# Master10.net
KiCad netlist of a schematic drawn in EAGLE
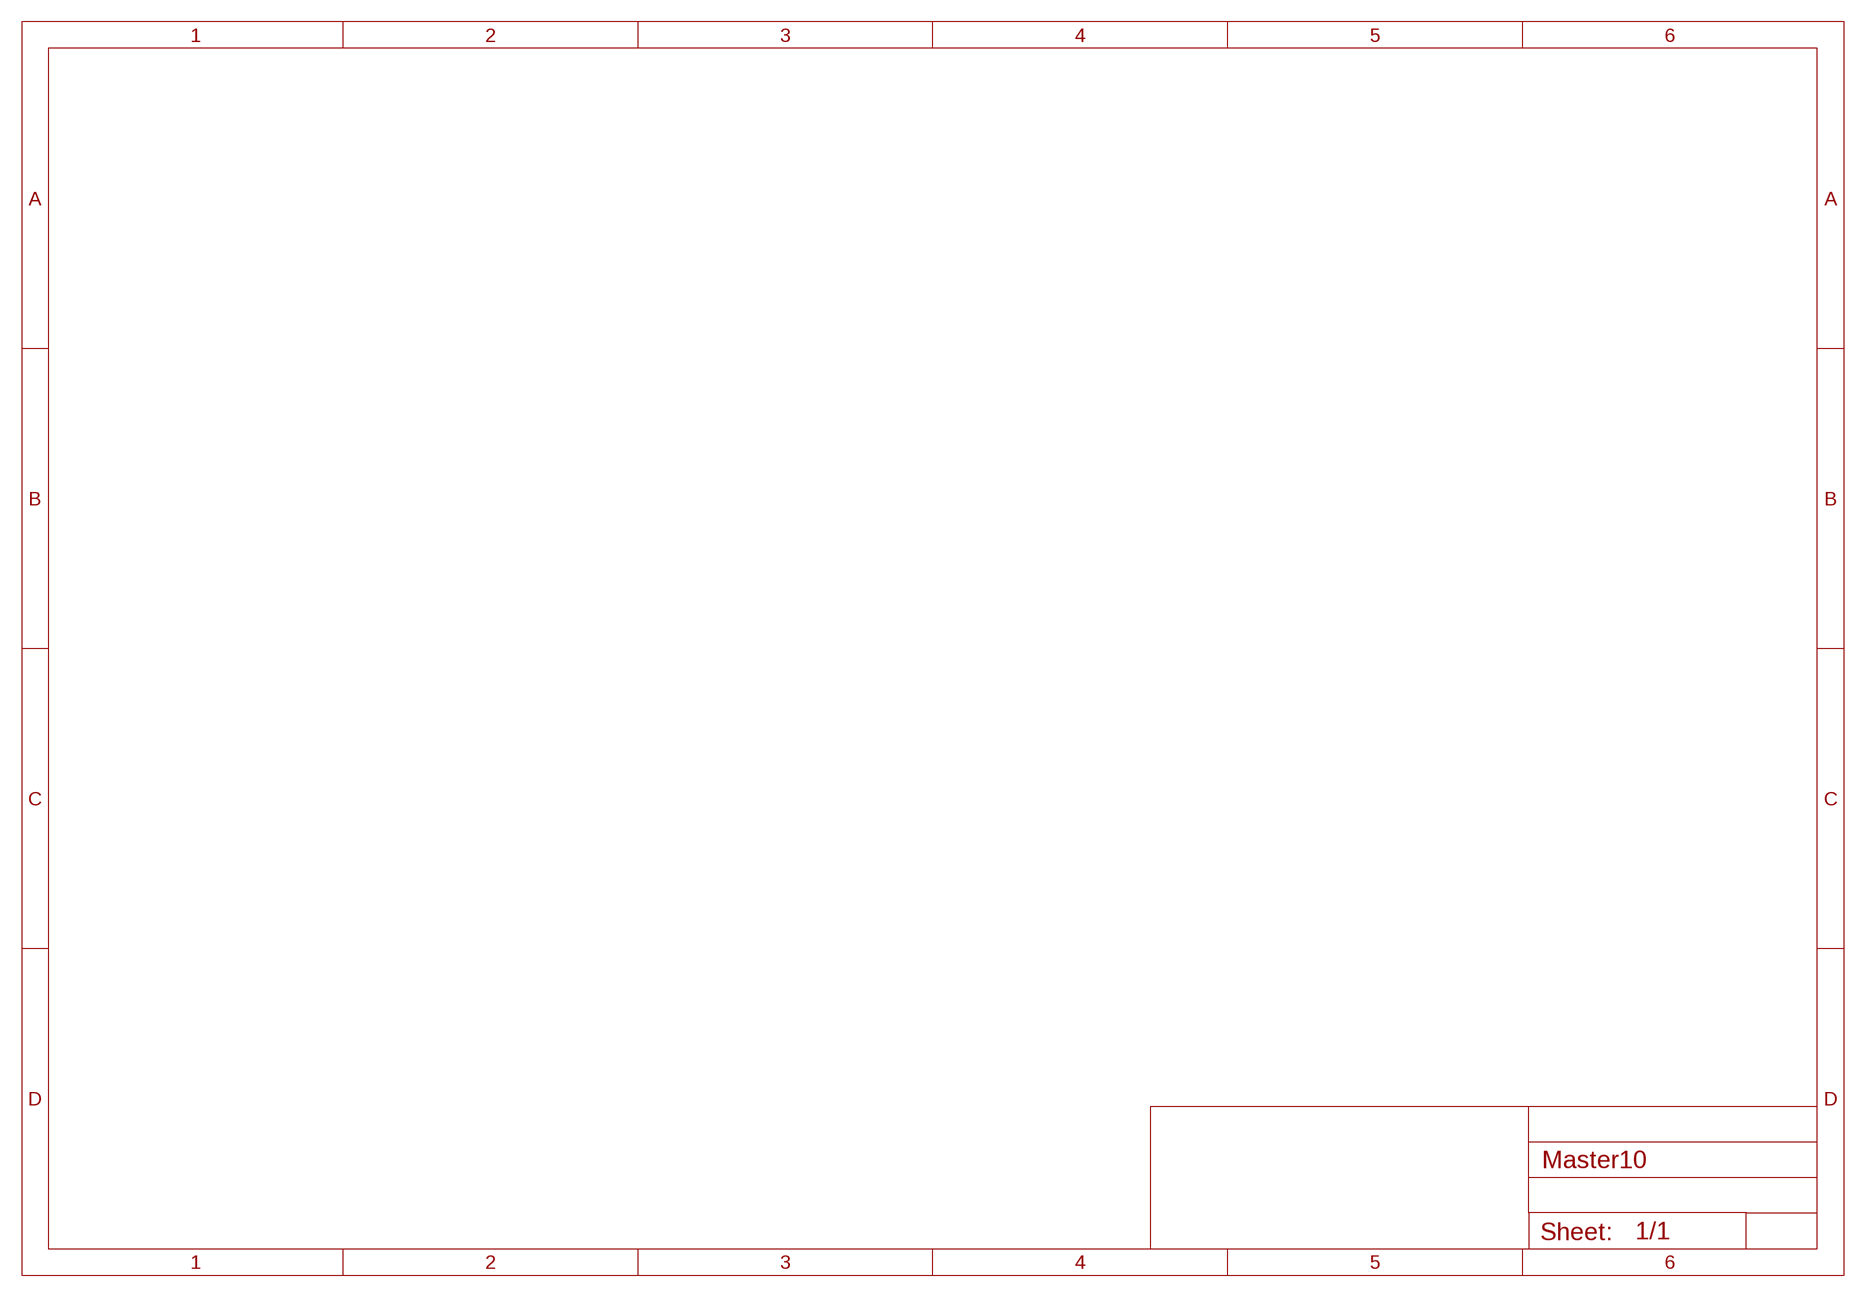
[diagram p0: schematic, sheet 1, part 1 of 2]
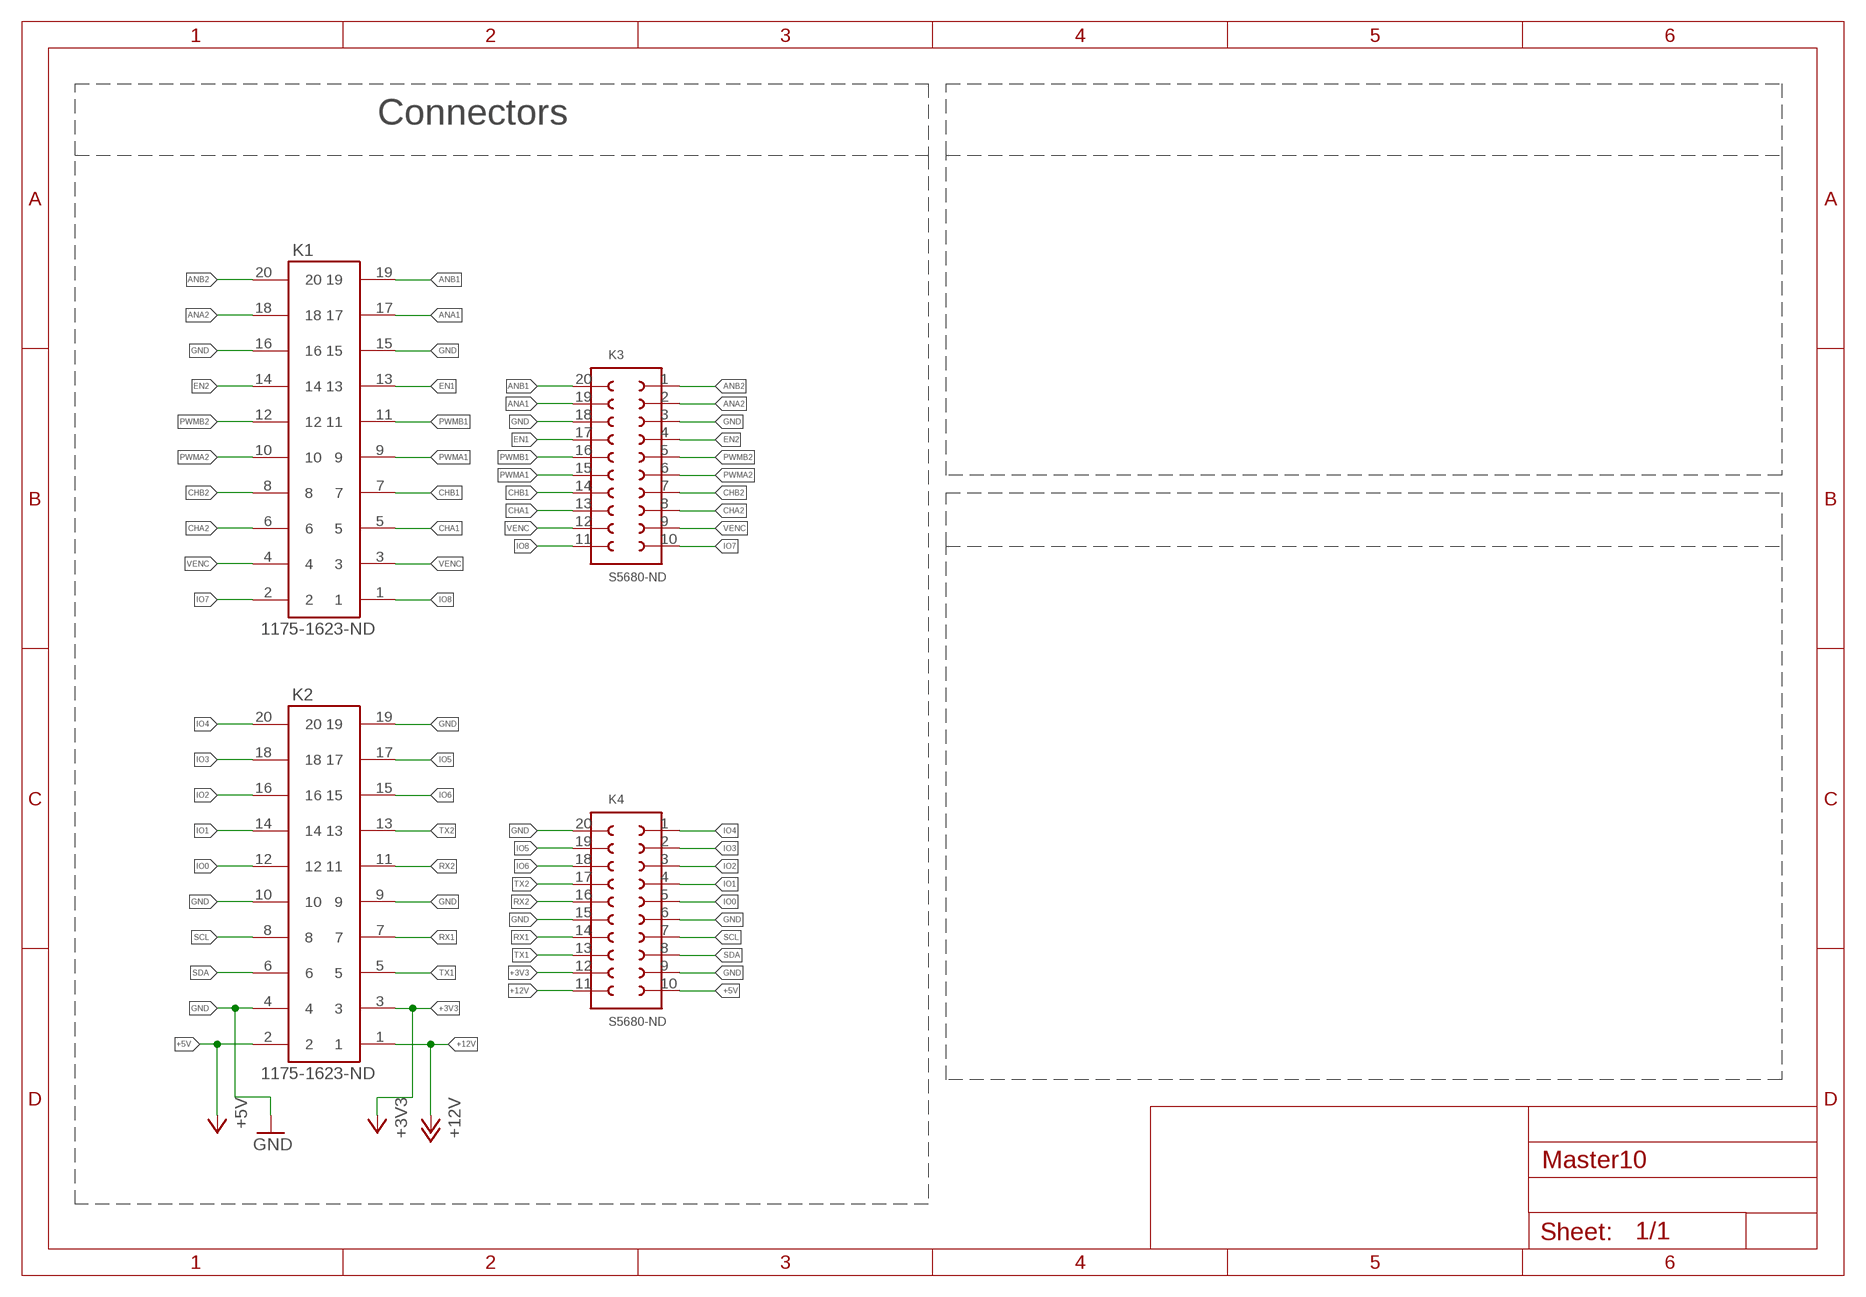
[diagram p1: schematic, sheet 1, part 2 of 2]

(export (version "E")
  (design (tool "Eeschema 10.0.6"))
  (components
    (comp (ref "K1")
      (value "1175-1623-ND")
      (footprint "eagle-import:612X2020621")
      (libsource (lib "eagle-import") (part "612X2020621"))
    )
    (comp (ref "K2")
      (value "1175-1623-ND")
      (footprint "eagle-import:612X2020621")
      (libsource (lib "eagle-import") (part "612X2020621"))
    )
    (comp (ref "K3")
      (value "S5680-ND")
      (footprint "eagle-import:61002021821")
      (libsource (lib "eagle-import") (part "61002021821"))
    )
    (comp (ref "K4")
      (value "S5680-ND")
      (footprint "eagle-import:61002021821")
      (libsource (lib "eagle-import") (part "61002021821"))
    )
  )
  (nets
    (net (code "1") (name "+3V3") (class "Default")
      (node (ref "K2") (pin "3") (pinfunction "3_3") (pintype "passive"))
      (node (ref "K4") (pin "12") (pinfunction "12_12") (pintype "passive"))
    )
    (net (code "2") (name "+5V") (class "Default")
      (node (ref "K2") (pin "2") (pinfunction "2_2") (pintype "passive"))
      (node (ref "K4") (pin "10") (pinfunction "10_10") (pintype "passive"))
    )
    (net (code "3") (name "+12V") (class "Default")
      (node (ref "K2") (pin "1") (pinfunction "1_1") (pintype "passive"))
      (node (ref "K4") (pin "11") (pinfunction "11_11") (pintype "passive"))
    )
    (net (code "4") (name "ANA1") (class "Default")
      (node (ref "K1") (pin "17") (pinfunction "17_17") (pintype "passive"))
      (node (ref "K3") (pin "19") (pinfunction "19_19") (pintype "passive"))
    )
    (net (code "5") (name "ANA2") (class "Default")
      (node (ref "K1") (pin "18") (pinfunction "18_18") (pintype "passive"))
      (node (ref "K3") (pin "2") (pinfunction "2_2") (pintype "passive"))
    )
    (net (code "6") (name "ANB1") (class "Default")
      (node (ref "K1") (pin "19") (pinfunction "19_19") (pintype "passive"))
      (node (ref "K3") (pin "20") (pinfunction "20_20") (pintype "passive"))
    )
    (net (code "7") (name "ANB2") (class "Default")
      (node (ref "K1") (pin "20") (pinfunction "20_20") (pintype "passive"))
      (node (ref "K3") (pin "1") (pinfunction "1_1") (pintype "passive"))
    )
    (net (code "8") (name "CHA1") (class "Default")
      (node (ref "K1") (pin "5") (pinfunction "5_5") (pintype "passive"))
      (node (ref "K3") (pin "13") (pinfunction "13_13") (pintype "passive"))
    )
    (net (code "9") (name "CHA2") (class "Default")
      (node (ref "K1") (pin "6") (pinfunction "6_6") (pintype "passive"))
      (node (ref "K3") (pin "8") (pinfunction "8_8") (pintype "passive"))
    )
    (net (code "10") (name "CHB1") (class "Default")
      (node (ref "K1") (pin "7") (pinfunction "7_7") (pintype "passive"))
      (node (ref "K3") (pin "14") (pinfunction "14_14") (pintype "passive"))
    )
    (net (code "11") (name "CHB2") (class "Default")
      (node (ref "K1") (pin "8") (pinfunction "8_8") (pintype "passive"))
      (node (ref "K3") (pin "7") (pinfunction "7_7") (pintype "passive"))
    )
    (net (code "12") (name "EN1") (class "Default")
      (node (ref "K1") (pin "13") (pinfunction "13_13") (pintype "passive"))
      (node (ref "K3") (pin "17") (pinfunction "17_17") (pintype "passive"))
    )
    (net (code "13") (name "EN2") (class "Default")
      (node (ref "K1") (pin "14") (pinfunction "14_14") (pintype "passive"))
      (node (ref "K3") (pin "4") (pinfunction "4_4") (pintype "passive"))
    )
    (net (code "14") (name "GND") (class "Default")
      (node (ref "K1") (pin "15") (pinfunction "15_15") (pintype "passive"))
      (node (ref "K1") (pin "16") (pinfunction "16_16") (pintype "passive"))
      (node (ref "K2") (pin "10") (pinfunction "10_10") (pintype "passive"))
      (node (ref "K2") (pin "19") (pinfunction "19_19") (pintype "passive"))
      (node (ref "K2") (pin "4") (pinfunction "4_4") (pintype "passive"))
      (node (ref "K2") (pin "9") (pinfunction "9_9") (pintype "passive"))
      (node (ref "K3") (pin "18") (pinfunction "18_18") (pintype "passive"))
      (node (ref "K3") (pin "3") (pinfunction "3_3") (pintype "passive"))
      (node (ref "K4") (pin "15") (pinfunction "15_15") (pintype "passive"))
      (node (ref "K4") (pin "20") (pinfunction "20_20") (pintype "passive"))
      (node (ref "K4") (pin "6") (pinfunction "6_6") (pintype "passive"))
      (node (ref "K4") (pin "9") (pinfunction "9_9") (pintype "passive"))
    )
    (net (code "15") (name "IO0") (class "Default")
      (node (ref "K2") (pin "12") (pinfunction "12_12") (pintype "passive"))
      (node (ref "K4") (pin "5") (pinfunction "5_5") (pintype "passive"))
    )
    (net (code "16") (name "IO1") (class "Default")
      (node (ref "K2") (pin "14") (pinfunction "14_14") (pintype "passive"))
      (node (ref "K4") (pin "4") (pinfunction "4_4") (pintype "passive"))
    )
    (net (code "17") (name "IO2") (class "Default")
      (node (ref "K2") (pin "16") (pinfunction "16_16") (pintype "passive"))
      (node (ref "K4") (pin "3") (pinfunction "3_3") (pintype "passive"))
    )
    (net (code "18") (name "IO3") (class "Default")
      (node (ref "K2") (pin "18") (pinfunction "18_18") (pintype "passive"))
      (node (ref "K4") (pin "2") (pinfunction "2_2") (pintype "passive"))
    )
    (net (code "19") (name "IO4") (class "Default")
      (node (ref "K2") (pin "20") (pinfunction "20_20") (pintype "passive"))
      (node (ref "K4") (pin "1") (pinfunction "1_1") (pintype "passive"))
    )
    (net (code "20") (name "IO5") (class "Default")
      (node (ref "K2") (pin "17") (pinfunction "17_17") (pintype "passive"))
      (node (ref "K4") (pin "19") (pinfunction "19_19") (pintype "passive"))
    )
    (net (code "21") (name "IO6") (class "Default")
      (node (ref "K2") (pin "15") (pinfunction "15_15") (pintype "passive"))
      (node (ref "K4") (pin "18") (pinfunction "18_18") (pintype "passive"))
    )
    (net (code "22") (name "IO7") (class "Default")
      (node (ref "K1") (pin "2") (pinfunction "2_2") (pintype "passive"))
      (node (ref "K3") (pin "10") (pinfunction "10_10") (pintype "passive"))
    )
    (net (code "23") (name "IO8") (class "Default")
      (node (ref "K1") (pin "1") (pinfunction "1_1") (pintype "passive"))
      (node (ref "K3") (pin "11") (pinfunction "11_11") (pintype "passive"))
    )
    (net (code "24") (name "PWMA1") (class "Default")
      (node (ref "K1") (pin "9") (pinfunction "9_9") (pintype "passive"))
      (node (ref "K3") (pin "15") (pinfunction "15_15") (pintype "passive"))
    )
    (net (code "25") (name "PWMA2") (class "Default")
      (node (ref "K1") (pin "10") (pinfunction "10_10") (pintype "passive"))
      (node (ref "K3") (pin "6") (pinfunction "6_6") (pintype "passive"))
    )
    (net (code "26") (name "PWMB1") (class "Default")
      (node (ref "K1") (pin "11") (pinfunction "11_11") (pintype "passive"))
      (node (ref "K3") (pin "16") (pinfunction "16_16") (pintype "passive"))
    )
    (net (code "27") (name "PWMB2") (class "Default")
      (node (ref "K1") (pin "12") (pinfunction "12_12") (pintype "passive"))
      (node (ref "K3") (pin "5") (pinfunction "5_5") (pintype "passive"))
    )
    (net (code "28") (name "RX1") (class "Default")
      (node (ref "K2") (pin "7") (pinfunction "7_7") (pintype "passive"))
      (node (ref "K4") (pin "14") (pinfunction "14_14") (pintype "passive"))
    )
    (net (code "29") (name "RX2") (class "Default")
      (node (ref "K2") (pin "11") (pinfunction "11_11") (pintype "passive"))
      (node (ref "K4") (pin "16") (pinfunction "16_16") (pintype "passive"))
    )
    (net (code "30") (name "SCL") (class "Default")
      (node (ref "K2") (pin "8") (pinfunction "8_8") (pintype "passive"))
      (node (ref "K4") (pin "7") (pinfunction "7_7") (pintype "passive"))
    )
    (net (code "31") (name "SDA") (class "Default")
      (node (ref "K2") (pin "6") (pinfunction "6_6") (pintype "passive"))
      (node (ref "K4") (pin "8") (pinfunction "8_8") (pintype "passive"))
    )
    (net (code "32") (name "TX1") (class "Default")
      (node (ref "K2") (pin "5") (pinfunction "5_5") (pintype "passive"))
      (node (ref "K4") (pin "13") (pinfunction "13_13") (pintype "passive"))
    )
    (net (code "33") (name "TX2") (class "Default")
      (node (ref "K2") (pin "13") (pinfunction "13_13") (pintype "passive"))
      (node (ref "K4") (pin "17") (pinfunction "17_17") (pintype "passive"))
    )
    (net (code "34") (name "VENC") (class "Default")
      (node (ref "K1") (pin "3") (pinfunction "3_3") (pintype "passive"))
      (node (ref "K1") (pin "4") (pinfunction "4_4") (pintype "passive"))
      (node (ref "K3") (pin "12") (pinfunction "12_12") (pintype "passive"))
      (node (ref "K3") (pin "9") (pinfunction "9_9") (pintype "passive"))
    )
  )
)
